# OMD_Fets_80A.net
KiCad netlist of a schematic drawn in Altium Designer
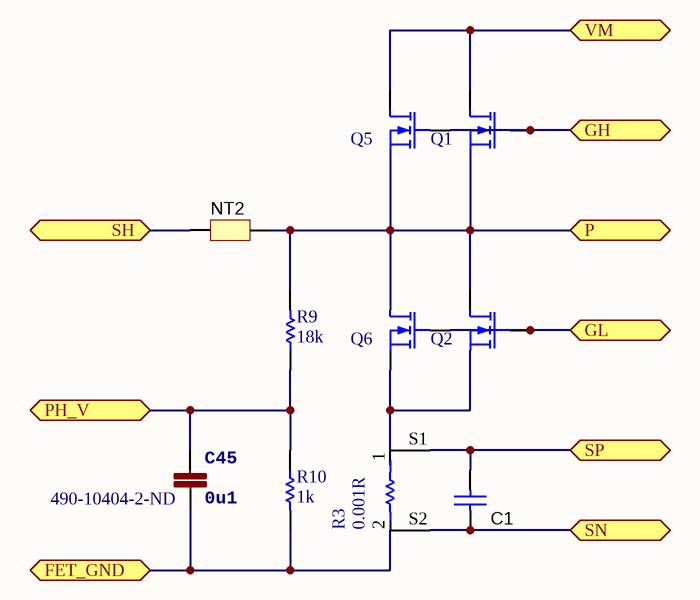
[diagram p0: OMD_Fets_80A.SchDoc]

(export (version "E")
  (design (tool "Eeschema 10.0.6"))
  (components
    (comp (ref "C1")
      (value "~")
      (footprint "0603-CAP")
      (description "CAP, CERM, 1000pF, 16V, +/-10%, X7R, 0603")
      (libsource (lib "OMD") (part "GRM188R71C102KA01D"))
    )
    (comp (ref "C45")
      (value "0u1")
      (footprint "0201-cap")
      (description "CAP CER 0.1UF 6V Y5V 0201")
      (fields (field (name "SUPPLIER PART NUMBER 1") "490-10404-2-ND"))
      (libsource (lib "OMD") (part "CAP0402"))
    )
    (comp (ref "NT2")
      (value "Net-Tie")
      (footprint "Net-Tie_10mil")
      (description "Single point connection between nets.")
      (libsource (lib "OMD") (part "Net-Tie"))
    )
    (comp (ref "Q1")
      (value "MOSFET-N")
      (footprint "Q5B")
      (description "N-Channel MOSFET")
      (libsource (lib "OMD") (part "MOSFET-N"))
    )
    (comp (ref "Q2")
      (value "MOSFET-N")
      (footprint "Q5B")
      (description "N-Channel MOSFET")
      (libsource (lib "OMD") (part "MOSFET-N"))
    )
    (comp (ref "Q5")
      (value "MOSFET-N")
      (footprint "Q5B")
      (description "N-Channel MOSFET")
      (libsource (lib "OMD") (part "MOSFET-N"))
    )
    (comp (ref "Q6")
      (value "MOSFET-N")
      (footprint "Q5B")
      (description "N-Channel MOSFET")
      (libsource (lib "") (part "MOSFET-N_1"))
    )
    (comp (ref "R3")
      (value "0.001R")
      (footprint "4RESC5125X09N")
      (description "2W, 0.001R 5025 current sense resistor")
      (fields (field (name "Comment") "Current sense resistor"))
      (libsource (lib "OMD") (part "WSLP20101L000FEK"))
    )
    (comp (ref "R9")
      (value "18k")
      (footprint "R0805")
      (description "RES SMD 18K OHM 1% 1/8W 0805")
      (fields (field (name "Comment") "RES"))
      (libsource (lib "OMD") (part "RES"))
    )
    (comp (ref "R10")
      (value "1k")
      (footprint "R0805")
      (description "RES SMD 1K OHM 1% 1/8W 0805")
      (fields (field (name "Comment") "RES"))
      (libsource (lib "OMD") (part "RES"))
    )
  )
  (nets
    (net (code "1") (name "/FET_GND") (class "Default")
      (node (ref "C45") (pin "2") (pinfunction "2_2") (pintype "passive"))
      (node (ref "R10") (pin "2") (pinfunction "2_2") (pintype "passive"))
      (node (ref "R3") (pin "2") (pinfunction "2_2") (pintype "passive"))
    )
    (net (code "2") (name "/GH") (class "Default")
      (node (ref "Q1") (pin "G") (pinfunction "G_G") (pintype "passive"))
      (node (ref "Q5") (pin "G") (pinfunction "G_G") (pintype "passive"))
    )
    (net (code "3") (name "/GL") (class "Default")
      (node (ref "Q2") (pin "G") (pinfunction "G_G") (pintype "passive"))
      (node (ref "Q6") (pin "G") (pinfunction "G_G") (pintype "passive"))
    )
    (net (code "4") (name "/P") (class "Default")
      (node (ref "NT2") (pin "2") (pinfunction "2_2") (pintype "passive"))
      (node (ref "Q1") (pin "S") (pinfunction "S_S") (pintype "passive"))
      (node (ref "Q2") (pin "D") (pinfunction "D_D") (pintype "passive"))
      (node (ref "Q5") (pin "S") (pinfunction "S_S") (pintype "passive"))
      (node (ref "Q6") (pin "D") (pinfunction "D_D") (pintype "passive"))
      (node (ref "R9") (pin "2") (pinfunction "2_2") (pintype "passive"))
    )
    (net (code "5") (name "/PH_V") (class "Default")
      (node (ref "C45") (pin "1") (pinfunction "1_1") (pintype "passive"))
      (node (ref "R10") (pin "1") (pinfunction "1_1") (pintype "passive"))
      (node (ref "R9") (pin "1") (pinfunction "1_1") (pintype "passive"))
    )
    (net (code "6") (name "/SH") (class "Default")
      (node (ref "NT2") (pin "1") (pinfunction "1_1") (pintype "passive"))
    )
    (net (code "7") (name "/SN") (class "Default")
      (node (ref "C1") (pin "2") (pinfunction "2_2") (pintype "passive"))
      (node (ref "R3") (pin "S2") (pinfunction "S2_S2") (pintype "passive"))
    )
    (net (code "8") (name "/SP") (class "Default")
      (node (ref "C1") (pin "1") (pinfunction "1_1") (pintype "passive"))
      (node (ref "R3") (pin "S1") (pinfunction "S1_S1") (pintype "passive"))
    )
    (net (code "9") (name "/VM") (class "Default")
      (node (ref "Q1") (pin "D") (pinfunction "D_D") (pintype "passive"))
      (node (ref "Q5") (pin "D") (pinfunction "D_D") (pintype "passive"))
    )
    (net (code "10") (name "Net-(Q2-PadS)") (class "Default")
      (node (ref "Q2") (pin "S") (pinfunction "S_S") (pintype "passive"))
      (node (ref "Q6") (pin "S") (pinfunction "S_S") (pintype "passive"))
      (node (ref "R3") (pin "1") (pinfunction "1_1") (pintype "passive"))
    )
  )
)
